# SOT223_Breakout_Board.net
KiCad netlist of a schematic drawn in EAGLE
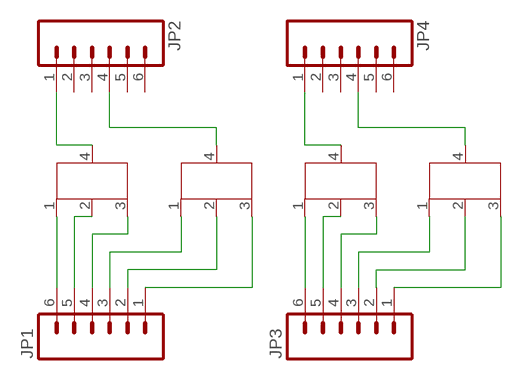
[diagram p0: schematic, sheet 1]

(export (version "E")
  (design (tool "Eeschema 10.0.6"))
  (components
    (comp (ref "JP1")
      (value "M06")
      (footprint "eagle-import:1X06")
      (libsource (lib "eagle-import") (part "M06"))
    )
    (comp (ref "JP2")
      (value "M06")
      (footprint "eagle-import:1X06")
      (libsource (lib "eagle-import") (part "M06"))
    )
    (comp (ref "JP3")
      (value "M06")
      (footprint "eagle-import:1X06")
      (libsource (lib "eagle-import") (part "M06"))
    )
    (comp (ref "JP4")
      (value "M06")
      (footprint "eagle-import:1X06")
      (libsource (lib "eagle-import") (part "M06"))
    )
    (comp (ref "U$1")
      (value "SOT223")
      (footprint "eagle-import:SOT223")
      (libsource (lib "eagle-import") (part "SOT223"))
    )
    (comp (ref "U$2")
      (value "SOT223")
      (footprint "eagle-import:SOT223")
      (libsource (lib "eagle-import") (part "SOT223"))
    )
    (comp (ref "U$3")
      (value "SOT223")
      (footprint "eagle-import:SOT223")
      (libsource (lib "eagle-import") (part "SOT223"))
    )
    (comp (ref "U$4")
      (value "SOT223")
      (footprint "eagle-import:SOT223")
      (libsource (lib "eagle-import") (part "SOT223"))
    )
  )
  (nets
    (net (code "1") (name "Net-(JP1-Pad1)") (class "Default")
      (node (ref "JP1") (pin "1") (pinfunction "1_1") (pintype "passive"))
      (node (ref "U$3") (pin "3") (pinfunction "3_3") (pintype "bidirectional"))
    )
    (net (code "2") (name "Net-(JP1-Pad2)") (class "Default")
      (node (ref "JP1") (pin "2") (pinfunction "2_2") (pintype "passive"))
      (node (ref "U$3") (pin "2") (pinfunction "2_2") (pintype "bidirectional"))
    )
    (net (code "3") (name "Net-(JP1-Pad3)") (class "Default")
      (node (ref "JP1") (pin "3") (pinfunction "3_3") (pintype "passive"))
      (node (ref "U$3") (pin "1") (pinfunction "1_1") (pintype "bidirectional"))
    )
    (net (code "4") (name "Net-(JP1-Pad4)") (class "Default")
      (node (ref "JP1") (pin "4") (pinfunction "4_4") (pintype "passive"))
      (node (ref "U$1") (pin "3") (pinfunction "3_3") (pintype "bidirectional"))
    )
    (net (code "5") (name "Net-(JP1-Pad5)") (class "Default")
      (node (ref "JP1") (pin "5") (pinfunction "5_5") (pintype "passive"))
      (node (ref "U$1") (pin "2") (pinfunction "2_2") (pintype "bidirectional"))
    )
    (net (code "6") (name "Net-(JP1-Pad6)") (class "Default")
      (node (ref "JP1") (pin "6") (pinfunction "6_6") (pintype "passive"))
      (node (ref "U$1") (pin "1") (pinfunction "1_1") (pintype "bidirectional"))
    )
    (net (code "7") (name "Net-(JP2-Pad1)") (class "Default")
      (node (ref "JP2") (pin "1") (pinfunction "1_1") (pintype "passive"))
      (node (ref "U$1") (pin "4") (pinfunction "4_4") (pintype "bidirectional"))
    )
    (net (code "8") (name "Net-(JP2-Pad4)") (class "Default")
      (node (ref "JP2") (pin "4") (pinfunction "4_4") (pintype "passive"))
      (node (ref "U$3") (pin "4") (pinfunction "4_4") (pintype "bidirectional"))
    )
    (net (code "9") (name "Net-(JP3-Pad1)") (class "Default")
      (node (ref "JP3") (pin "1") (pinfunction "1_1") (pintype "passive"))
      (node (ref "U$4") (pin "3") (pinfunction "3_3") (pintype "bidirectional"))
    )
    (net (code "10") (name "Net-(JP3-Pad2)") (class "Default")
      (node (ref "JP3") (pin "2") (pinfunction "2_2") (pintype "passive"))
      (node (ref "U$4") (pin "2") (pinfunction "2_2") (pintype "bidirectional"))
    )
    (net (code "11") (name "Net-(JP3-Pad3)") (class "Default")
      (node (ref "JP3") (pin "3") (pinfunction "3_3") (pintype "passive"))
      (node (ref "U$4") (pin "1") (pinfunction "1_1") (pintype "bidirectional"))
    )
    (net (code "12") (name "Net-(JP3-Pad4)") (class "Default")
      (node (ref "JP3") (pin "4") (pinfunction "4_4") (pintype "passive"))
      (node (ref "U$2") (pin "3") (pinfunction "3_3") (pintype "bidirectional"))
    )
    (net (code "13") (name "Net-(JP3-Pad5)") (class "Default")
      (node (ref "JP3") (pin "5") (pinfunction "5_5") (pintype "passive"))
      (node (ref "U$2") (pin "2") (pinfunction "2_2") (pintype "bidirectional"))
    )
    (net (code "14") (name "Net-(JP3-Pad6)") (class "Default")
      (node (ref "JP3") (pin "6") (pinfunction "6_6") (pintype "passive"))
      (node (ref "U$2") (pin "1") (pinfunction "1_1") (pintype "bidirectional"))
    )
    (net (code "15") (name "Net-(JP4-Pad1)") (class "Default")
      (node (ref "JP4") (pin "1") (pinfunction "1_1") (pintype "passive"))
      (node (ref "U$2") (pin "4") (pinfunction "4_4") (pintype "bidirectional"))
    )
    (net (code "16") (name "Net-(JP4-Pad4)") (class "Default")
      (node (ref "JP4") (pin "4") (pinfunction "4_4") (pintype "passive"))
      (node (ref "U$4") (pin "4") (pinfunction "4_4") (pintype "bidirectional"))
    )
    (net (code "17") (name "unconnected-(JP2-Pad2)") (class "Default")
      (node (ref "JP2") (pin "2") (pinfunction "2_2") (pintype "passive"))
    )
    (net (code "18") (name "unconnected-(JP2-Pad3)") (class "Default")
      (node (ref "JP2") (pin "3") (pinfunction "3_3") (pintype "passive"))
    )
    (net (code "19") (name "unconnected-(JP2-Pad5)") (class "Default")
      (node (ref "JP2") (pin "5") (pinfunction "5_5") (pintype "passive"))
    )
    (net (code "20") (name "unconnected-(JP2-Pad6)") (class "Default")
      (node (ref "JP2") (pin "6") (pinfunction "6_6") (pintype "passive"))
    )
    (net (code "21") (name "unconnected-(JP4-Pad2)") (class "Default")
      (node (ref "JP4") (pin "2") (pinfunction "2_2") (pintype "passive"))
    )
    (net (code "22") (name "unconnected-(JP4-Pad3)") (class "Default")
      (node (ref "JP4") (pin "3") (pinfunction "3_3") (pintype "passive"))
    )
    (net (code "23") (name "unconnected-(JP4-Pad5)") (class "Default")
      (node (ref "JP4") (pin "5") (pinfunction "5_5") (pintype "passive"))
    )
    (net (code "24") (name "unconnected-(JP4-Pad6)") (class "Default")
      (node (ref "JP4") (pin "6") (pinfunction "6_6") (pintype "passive"))
    )
  )
)
